# Clock.net
KiCad netlist of a schematic drawn in EAGLE
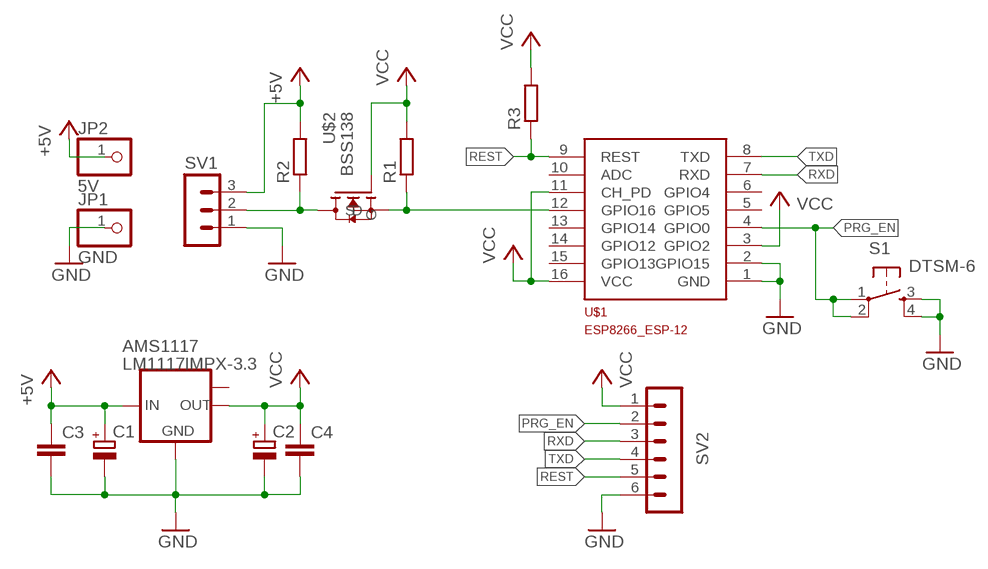
[diagram p0: schematic, sheet 1]

(export (version "E")
  (design (tool "Eeschema 10.0.6"))
  (components
    (comp (ref "AMS1117")
      (value "LM1117IMPX-3.3")
      (footprint "eagle-import:SOT223")
      (libsource (lib "eagle-import") (part "LM1117IMPX-3.3"))
    )
    (comp (ref "C1")
      (value "CPOL-EUE3.5-8")
      (footprint "eagle-import:E3,5-8")
      (libsource (lib "eagle-import") (part "CPOL-EUE3.5-8"))
    )
    (comp (ref "C2")
      (value "CPOL-EUE3.5-8")
      (footprint "eagle-import:E3,5-8")
      (libsource (lib "eagle-import") (part "CPOL-EUE3.5-8"))
    )
    (comp (ref "C3")
      (value "C-EUC0805")
      (footprint "eagle-import:C0805")
      (libsource (lib "eagle-import") (part "C-EUC0805"))
    )
    (comp (ref "C4")
      (value "C-EUC0805")
      (footprint "eagle-import:C0805")
      (libsource (lib "eagle-import") (part "C-EUC0805"))
    )
    (comp (ref "JP1")
      (value "GND")
      (footprint "eagle-import:1X01")
      (libsource (lib "eagle-import") (part "PINHD-1X1"))
    )
    (comp (ref "JP2")
      (value "5V")
      (footprint "eagle-import:1X01")
      (libsource (lib "eagle-import") (part "PINHD-1X1"))
    )
    (comp (ref "R1")
      (value "R-EU_R0805")
      (footprint "eagle-import:R0805")
      (libsource (lib "eagle-import") (part "R-EU_R0805"))
    )
    (comp (ref "R2")
      (value "R-EU_R0805")
      (footprint "eagle-import:R0805")
      (libsource (lib "eagle-import") (part "R-EU_R0805"))
    )
    (comp (ref "R3")
      (value "R-EU_R0805")
      (footprint "eagle-import:R0805")
      (libsource (lib "eagle-import") (part "R-EU_R0805"))
    )
    (comp (ref "S1")
      (value "DTSM-6")
      (footprint "eagle-import:DTSM-6")
      (libsource (lib "eagle-import") (part "DTSM-6"))
    )
    (comp (ref "SV1")
      (value "MA03-1")
      (footprint "eagle-import:MA03-1")
      (libsource (lib "eagle-import") (part "MA03-1"))
    )
    (comp (ref "SV2")
      (value "MA06-1")
      (footprint "eagle-import:MA06-1")
      (libsource (lib "eagle-import") (part "MA06-1"))
    )
    (comp (ref "U$1")
      (value "ESP8266_ESP-12")
      (footprint "eagle-import:ESP8266-ESP12")
      (libsource (lib "eagle-import") (part "ESP8266_ESP-12"))
    )
    (comp (ref "U$2")
      (value "BSS138")
      (footprint "eagle-import:BSS138")
      (fields (field (name "MF") "Fairchild Semiconductor"))
      (libsource (lib "eagle-import") (part "BSS138"))
    )
  )
  (nets
    (net (code "1") (name "+5V") (class "Default")
      (node (ref "AMS1117") (pin "3") (pinfunction "IN_3") (pintype "input"))
      (node (ref "C1") (pin "+") (pinfunction "+_+") (pintype "passive"))
      (node (ref "C3") (pin "1") (pinfunction "1_1") (pintype "passive"))
      (node (ref "JP2") (pin "1") (pinfunction "1_1") (pintype "passive"))
      (node (ref "R2") (pin "2") (pinfunction "2_2") (pintype "passive"))
      (node (ref "SV1") (pin "3") (pinfunction "3_3") (pintype "passive"))
    )
    (net (code "2") (name "GND") (class "Default")
      (node (ref "AMS1117") (pin "1") (pinfunction "GND_1") (pintype "input"))
      (node (ref "C1") (pin "-") (pinfunction "-_-") (pintype "passive"))
      (node (ref "C2") (pin "-") (pinfunction "-_-") (pintype "passive"))
      (node (ref "C3") (pin "2") (pinfunction "2_2") (pintype "passive"))
      (node (ref "C4") (pin "2") (pinfunction "2_2") (pintype "passive"))
      (node (ref "JP1") (pin "1") (pinfunction "1_1") (pintype "passive"))
      (node (ref "S1") (pin "3") (pinfunction "3_3") (pintype "passive"))
      (node (ref "S1") (pin "4") (pinfunction "4_4") (pintype "passive"))
      (node (ref "SV1") (pin "1") (pinfunction "1_1") (pintype "passive"))
      (node (ref "SV2") (pin "6") (pinfunction "6_6") (pintype "passive"))
      (node (ref "U$1") (pin "1") (pinfunction "GND_1") (pintype "bidirectional"))
      (node (ref "U$1") (pin "2") (pinfunction "GPIO15_2") (pintype "bidirectional"))
    )
    (net (code "3") (name "Net-(R2-Pad1)") (class "Default")
      (node (ref "R2") (pin "1") (pinfunction "1_1") (pintype "passive"))
      (node (ref "SV1") (pin "2") (pinfunction "2_2") (pintype "passive"))
      (node (ref "U$2") (pin "D") (pinfunction "D_D") (pintype "passive"))
    )
    (net (code "4") (name "Net-(U$1-GPIO16)") (class "Default")
      (node (ref "R1") (pin "1") (pinfunction "1_1") (pintype "passive"))
      (node (ref "U$1") (pin "12") (pinfunction "GPIO16_12") (pintype "bidirectional"))
      (node (ref "U$2") (pin "S") (pinfunction "S_S") (pintype "passive"))
    )
    (net (code "5") (name "PRG_EN") (class "Default")
      (node (ref "S1") (pin "1") (pinfunction "1_1") (pintype "passive"))
      (node (ref "S1") (pin "2") (pinfunction "2_2") (pintype "passive"))
      (node (ref "SV2") (pin "2") (pinfunction "2_2") (pintype "passive"))
      (node (ref "U$1") (pin "4") (pinfunction "GPIO0_4") (pintype "bidirectional"))
    )
    (net (code "6") (name "REST") (class "Default")
      (node (ref "R3") (pin "1") (pinfunction "1_1") (pintype "passive"))
      (node (ref "SV2") (pin "5") (pinfunction "5_5") (pintype "passive"))
      (node (ref "U$1") (pin "9") (pinfunction "REST_9") (pintype "bidirectional"))
    )
    (net (code "7") (name "RXD") (class "Default")
      (node (ref "SV2") (pin "3") (pinfunction "3_3") (pintype "passive"))
      (node (ref "U$1") (pin "7") (pinfunction "RXD_7") (pintype "bidirectional"))
    )
    (net (code "8") (name "TXD") (class "Default")
      (node (ref "SV2") (pin "4") (pinfunction "4_4") (pintype "passive"))
      (node (ref "U$1") (pin "8") (pinfunction "TXD_8") (pintype "bidirectional"))
    )
    (net (code "9") (name "VCC") (class "Default")
      (node (ref "AMS1117") (pin "2") (pinfunction "OUT_2") (pintype "passive"))
      (node (ref "C2") (pin "+") (pinfunction "+_+") (pintype "passive"))
      (node (ref "C4") (pin "1") (pinfunction "1_1") (pintype "passive"))
      (node (ref "R1") (pin "2") (pinfunction "2_2") (pintype "passive"))
      (node (ref "R3") (pin "2") (pinfunction "2_2") (pintype "passive"))
      (node (ref "SV2") (pin "1") (pinfunction "1_1") (pintype "passive"))
      (node (ref "U$1") (pin "11") (pinfunction "CH_PD_11") (pintype "bidirectional"))
      (node (ref "U$1") (pin "16") (pinfunction "VCC_16") (pintype "bidirectional"))
      (node (ref "U$1") (pin "3") (pinfunction "GPIO2_3") (pintype "bidirectional"))
      (node (ref "U$2") (pin "G") (pinfunction "G_G") (pintype "passive"))
    )
    (net (code "10") (name "unconnected-(AMS1117-OUT1-PadTAB)") (class "Default")
      (node (ref "AMS1117") (pin "TAB") (pinfunction "OUT1_TAB") (pintype "passive"))
    )
    (net (code "11") (name "unconnected-(U$1-ADC-Pad10)") (class "Default")
      (node (ref "U$1") (pin "10") (pinfunction "ADC_10") (pintype "bidirectional"))
    )
    (net (code "12") (name "unconnected-(U$1-GPIO4-Pad6)") (class "Default")
      (node (ref "U$1") (pin "6") (pinfunction "GPIO4_6") (pintype "bidirectional"))
    )
    (net (code "13") (name "unconnected-(U$1-GPIO5-Pad5)") (class "Default")
      (node (ref "U$1") (pin "5") (pinfunction "GPIO5_5") (pintype "bidirectional"))
    )
    (net (code "14") (name "unconnected-(U$1-GPIO12-Pad14)") (class "Default")
      (node (ref "U$1") (pin "14") (pinfunction "GPIO12_14") (pintype "bidirectional"))
    )
    (net (code "15") (name "unconnected-(U$1-GPIO13-Pad15)") (class "Default")
      (node (ref "U$1") (pin "15") (pinfunction "GPIO13_15") (pintype "bidirectional"))
    )
    (net (code "16") (name "unconnected-(U$1-GPIO14-Pad13)") (class "Default")
      (node (ref "U$1") (pin "13") (pinfunction "GPIO14_13") (pintype "bidirectional"))
    )
  )
)
